# Sheet.net
KiCad netlist of a schematic drawn in Altium Designer
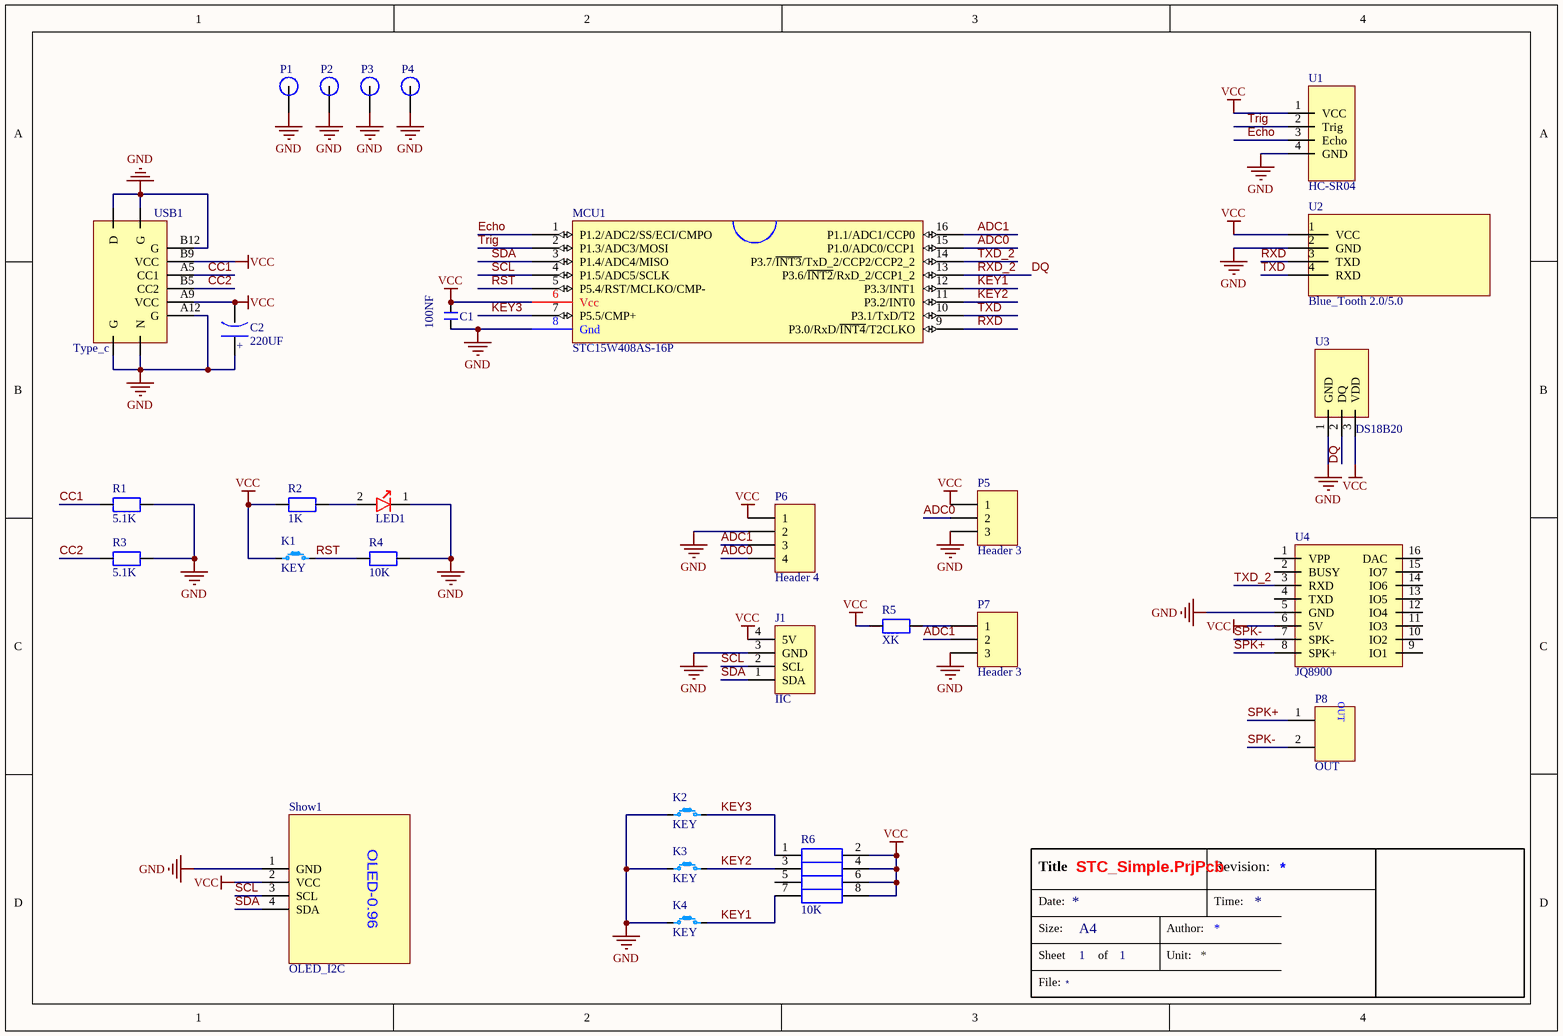
[diagram p0: Sheet.SchDoc]

(export (version "E")
  (design (tool "Eeschema 10.0.6"))
  (components
    (comp (ref "C1")
      (value "100NF")
      (footprint "CAP_0603")
      (description "CAP  12~50V")
      (libsource (lib "User") (part "CAP"))
    )
    (comp (ref "C2")
      (value "220UF")
      (footprint "CAP_PR_2.5_6.3_RA")
      (description "CAP 12V ~ 50V   电解电容")
      (libsource (lib "User") (part "CAP_BIG"))
    )
    (comp (ref "J1")
      (value "IIC")
      (footprint "IIC-XH2.54-4PIN")
      (description "Heard")
      (libsource (lib "User") (part "IIC"))
    )
    (comp (ref "K1")
      (value "KEY")
      (footprint "KEY_SMD")
      (description "Key")
      (libsource (lib "User") (part "KEY"))
    )
    (comp (ref "K2")
      (value "KEY")
      (footprint "SW_PB_3X6")
      (description "Key")
      (libsource (lib "User") (part "KEY"))
    )
    (comp (ref "K3")
      (value "KEY")
      (footprint "SW_PB_3X6")
      (description "Key")
      (libsource (lib "User") (part "KEY"))
    )
    (comp (ref "K4")
      (value "KEY")
      (footprint "SW_PB_3X6")
      (description "Key")
      (libsource (lib "User") (part "KEY"))
    )
    (comp (ref "LED1")
      (value "LED_R/G/B/Y")
      (footprint "LED_0603_R")
      (description "LED")
      (libsource (lib "User") (part "LED_SMT"))
    )
    (comp (ref "MCU1")
      (value "STC15W408AS-16P")
      (footprint "SOIC_16")
      (description "MCU")
      (libsource (lib "User") (part "STC15W-16"))
    )
    (comp (ref "P1")
      (value "铜柱6m")
      (footprint "M3x6_L-Type")
      (description "IN-OUT")
      (libsource (lib "User") (part "Pillar"))
    )
    (comp (ref "P2")
      (value "铜柱6m")
      (footprint "M3x6_L-Type")
      (description "IN-OUT")
      (libsource (lib "User") (part "Pillar"))
    )
    (comp (ref "P3")
      (value "铜柱6m")
      (footprint "M3x6_L-Type")
      (description "IN-OUT")
      (libsource (lib "User") (part "Pillar"))
    )
    (comp (ref "P4")
      (value "铜柱6m")
      (footprint "M3x6_L-Type")
      (description "IN-OUT")
      (libsource (lib "User") (part "Pillar"))
    )
    (comp (ref "P5")
      (value "Header 3")
      (footprint "Header 2.54X3")
      (description "Header, 3-Pin")
      (fields (field (name "PUBLISHER") "Altium Limited"))
      (libsource (lib "Miscellaneous Connectors") (part "Header 3"))
    )
    (comp (ref "P6")
      (value "Header 4")
      (footprint "Header F 2.54X4")
      (description "Header, 4-Pin")
      (fields (field (name "PUBLISHER") "Altium Limited"))
      (libsource (lib "Miscellaneous Connectors") (part "Header 4"))
    )
    (comp (ref "P7")
      (value "Header 3")
      (footprint "Header 2.54X3")
      (description "Header, 3-Pin")
      (fields (field (name "PUBLISHER") "Altium Limited"))
      (libsource (lib "Miscellaneous Connectors") (part "Header 3"))
    )
    (comp (ref "P8")
      (value "OUT")
      (footprint "XH2.54-WI-2P")
      (description "Header")
      (libsource (lib "User") (part "OUT_2PIN"))
    )
    (comp (ref "R1")
      (value "5.1K")
      (footprint "RESC_0603_2")
      (description "RES 贴片")
      (libsource (lib "User") (part "RES"))
    )
    (comp (ref "R2")
      (value "1K")
      (footprint "RESC_0603_2")
      (description "RES 贴片")
      (libsource (lib "User") (part "RES"))
    )
    (comp (ref "R3")
      (value "5.1K")
      (footprint "RESC_0603_2")
      (description "RES 贴片")
      (libsource (lib "User") (part "RES"))
    )
    (comp (ref "R4")
      (value "10K")
      (footprint "RESC_0603_2")
      (description "RES 贴片")
      (libsource (lib "User") (part "RES"))
    )
    (comp (ref "R5")
      (value "XK")
      (footprint "RESC_0603_2")
      (description "RES 贴片")
      (libsource (lib "User") (part "RES"))
    )
    (comp (ref "R6")
      (value "10K")
      (footprint "RESC_0603_4")
      (description "RES")
      (libsource (lib "User") (part "RES_P4"))
    )
    (comp (ref "Show1")
      (value "OLED_I2C")
      (footprint "OLED_I2C")
      (description "MODE")
      (libsource (lib "User") (part "OLED_I2C"))
    )
    (comp (ref "U1")
      (value "HC-SR04")
      (footprint "Ultrasonic")
      (description "Mode")
      (libsource (lib "User") (part "Ultrasonic"))
    )
    (comp (ref "U2")
      (value "Blue_Tooth 2.0/5.0")
      (footprint "uart-Haerd")
      (description "MODE")
      (libsource (lib "User") (part "HC-02/06"))
    )
    (comp (ref "U3")
      (value "DS18B20")
      (footprint "TO_92B")
      (description "MODE")
      (libsource (lib "User") (part "DS18B20"))
    )
    (comp (ref "U4")
      (value "JQ8900")
      (footprint "SpkMo")
      (description "MODE")
      (libsource (lib "User") (part "SPKMO_8900"))
    )
    (comp (ref "USB1")
      (value "Type_c")
      (footprint "USB-Type-c_6P")
      (description "USB")
      (libsource (lib "User") (part "USB-Type_c-6PIn"))
    )
  )
  (nets
    (net (code "1") (name "/ADC0") (class "Default")
      (node (ref "MCU1") (pin "15") (pinfunction "P1.0/ADC0/CCP1_15") (pintype "bidirectional"))
      (node (ref "P5") (pin "2") (pinfunction "2_2") (pintype "passive"))
      (node (ref "P6") (pin "4") (pinfunction "4_4") (pintype "passive"))
    )
    (net (code "2") (name "/ADC1") (class "Default")
      (node (ref "MCU1") (pin "16") (pinfunction "P1.1/ADC1/CCP0_16") (pintype "bidirectional"))
      (node (ref "P6") (pin "3") (pinfunction "3_3") (pintype "passive"))
      (node (ref "P7") (pin "2") (pinfunction "2_2") (pintype "passive"))
    )
    (net (code "3") (name "/CC1") (class "Default")
      (node (ref "R1") (pin "1") (pinfunction "1_1") (pintype "passive"))
      (node (ref "USB1") (pin "A5") (pinfunction "CC1_A5") (pintype "passive"))
    )
    (net (code "4") (name "/CC2") (class "Default")
      (node (ref "R3") (pin "1") (pinfunction "1_1") (pintype "passive"))
      (node (ref "USB1") (pin "B5") (pinfunction "CC2_B5") (pintype "passive"))
    )
    (net (code "5") (name "/DQ") (class "Default")
      (node (ref "MCU1") (pin "13") (pinfunction "P3.6/~{INT2}/RxD_2/CCP1_2_13") (pintype "bidirectional"))
      (node (ref "U3") (pin "2") (pinfunction "DQ_2") (pintype "passive"))
    )
    (net (code "6") (name "/Echo") (class "Default")
      (node (ref "MCU1") (pin "1") (pinfunction "P1.2/ADC2/SS/ECI/CMPO_1") (pintype "bidirectional"))
      (node (ref "U1") (pin "3") (pinfunction "Echo_3") (pintype "passive"))
    )
    (net (code "7") (name "/KEY1") (class "Default")
      (node (ref "K4") (pin "1") (pintype "passive"))
      (node (ref "MCU1") (pin "12") (pinfunction "P3.3/INT1_12") (pintype "bidirectional"))
      (node (ref "R6") (pin "7") (pinfunction "7_7") (pintype "passive"))
    )
    (net (code "8") (name "/KEY2") (class "Default")
      (node (ref "K3") (pin "1") (pintype "passive"))
      (node (ref "MCU1") (pin "11") (pinfunction "P3.2/INT0_11") (pintype "bidirectional"))
      (node (ref "R6") (pin "3") (pinfunction "3_3") (pintype "passive"))
    )
    (net (code "9") (name "/KEY3") (class "Default")
      (node (ref "K2") (pin "1") (pintype "passive"))
      (node (ref "MCU1") (pin "7") (pinfunction "P5.5/CMP+_7") (pintype "bidirectional"))
      (node (ref "R6") (pin "1") (pinfunction "1_1") (pintype "passive"))
    )
    (net (code "10") (name "/RST") (class "Default")
      (node (ref "K1") (pin "1") (pintype "passive"))
      (node (ref "MCU1") (pin "5") (pinfunction "P5.4/RST/MCLKO/CMP-_5") (pintype "bidirectional"))
      (node (ref "R4") (pin "1") (pinfunction "1_1") (pintype "passive"))
    )
    (net (code "11") (name "/RXD") (class "Default")
      (node (ref "MCU1") (pin "9") (pinfunction "P3.0/RxD/~{INT4}/T2CLKO_9") (pintype "bidirectional"))
      (node (ref "U2") (pin "3") (pinfunction "TXD_3") (pintype "passive"))
    )
    (net (code "12") (name "/SCL") (class "Default")
      (node (ref "J1") (pin "2") (pinfunction "SCL_2") (pintype "passive"))
      (node (ref "MCU1") (pin "4") (pinfunction "P1.5/ADC5/SCLK_4") (pintype "bidirectional"))
      (node (ref "Show1") (pin "3") (pinfunction "SCL_3") (pintype "passive"))
    )
    (net (code "13") (name "/SDA") (class "Default")
      (node (ref "J1") (pin "1") (pinfunction "SDA_1") (pintype "passive"))
      (node (ref "MCU1") (pin "3") (pinfunction "P1.4/ADC4/MISO_3") (pintype "bidirectional"))
      (node (ref "Show1") (pin "4") (pinfunction "SDA_4") (pintype "passive"))
    )
    (net (code "14") (name "/SPK+") (class "Default")
      (node (ref "P8") (pin "1") (pintype "passive"))
      (node (ref "U4") (pin "8") (pinfunction "SPK+_8") (pintype "passive"))
    )
    (net (code "15") (name "/SPK-") (class "Default")
      (node (ref "P8") (pin "2") (pintype "passive"))
      (node (ref "U4") (pin "7") (pinfunction "SPK-_7") (pintype "passive"))
    )
    (net (code "16") (name "/TXD") (class "Default")
      (node (ref "MCU1") (pin "10") (pinfunction "P3.1/TxD/T2_10") (pintype "bidirectional"))
      (node (ref "U2") (pin "4") (pinfunction "RXD_4") (pintype "passive"))
    )
    (net (code "17") (name "/TXD_2") (class "Default")
      (node (ref "MCU1") (pin "14") (pinfunction "P3.7/~{INT3}/TxD_2/CCP2/CCP2_2_14") (pintype "bidirectional"))
      (node (ref "U4") (pin "3") (pinfunction "RXD_3") (pintype "passive"))
    )
    (net (code "18") (name "/Trig") (class "Default")
      (node (ref "MCU1") (pin "2") (pinfunction "P1.3/ADC3/MOSI_2") (pintype "bidirectional"))
      (node (ref "U1") (pin "2") (pinfunction "Trig_2") (pintype "passive"))
    )
    (net (code "19") (name "GND") (class "Default")
      (node (ref "C1") (pin "1") (pinfunction "0_1") (pintype "passive"))
      (node (ref "C2") (pin "1") (pinfunction "0_1") (pintype "passive"))
      (node (ref "J1") (pin "3") (pinfunction "GND_3") (pintype "passive"))
      (node (ref "K2") (pin "2") (pintype "passive"))
      (node (ref "K3") (pin "2") (pintype "passive"))
      (node (ref "K4") (pin "2") (pintype "passive"))
      (node (ref "LED1") (pin "1") (pinfunction "-_1") (pintype "passive"))
      (node (ref "MCU1") (pin "8") (pinfunction "Gnd_8") (pintype "power_in"))
      (node (ref "P1") (pin "1") (pinfunction "IO_1") (pintype "passive"))
      (node (ref "P2") (pin "1") (pinfunction "IO_1") (pintype "passive"))
      (node (ref "P3") (pin "1") (pinfunction "IO_1") (pintype "passive"))
      (node (ref "P4") (pin "1") (pinfunction "IO_1") (pintype "passive"))
      (node (ref "P5") (pin "3") (pinfunction "3_3") (pintype "passive"))
      (node (ref "P6") (pin "2") (pinfunction "2_2") (pintype "passive"))
      (node (ref "P7") (pin "3") (pinfunction "3_3") (pintype "passive"))
      (node (ref "R1") (pin "2") (pinfunction "2_2") (pintype "passive"))
      (node (ref "R3") (pin "2") (pinfunction "2_2") (pintype "passive"))
      (node (ref "R4") (pin "2") (pinfunction "2_2") (pintype "passive"))
      (node (ref "Show1") (pin "1") (pinfunction "GND_1") (pintype "passive"))
      (node (ref "U1") (pin "4") (pinfunction "GND_4") (pintype "passive"))
      (node (ref "U2") (pin "2") (pinfunction "GND_2") (pintype "passive"))
      (node (ref "U3") (pin "1") (pinfunction "GND_1") (pintype "passive"))
      (node (ref "U4") (pin "5") (pinfunction "GND_5") (pintype "passive"))
      (node (ref "USB1") (pin "A") (pinfunction "G_A") (pintype "passive"))
      (node (ref "USB1") (pin "A12") (pinfunction "G_A12") (pintype "passive"))
      (node (ref "USB1") (pin "B") (pinfunction "N_B") (pintype "passive"))
      (node (ref "USB1") (pin "B12") (pinfunction "G_B12") (pintype "passive"))
      (node (ref "USB1") (pin "C") (pinfunction "D_C") (pintype "passive"))
      (node (ref "USB1") (pin "D") (pinfunction "G_D") (pintype "passive"))
    )
    (net (code "20") (name "Net-(LED1-+)") (class "Default")
      (node (ref "LED1") (pin "2") (pinfunction "+_2") (pintype "passive"))
      (node (ref "R2") (pin "2") (pinfunction "2_2") (pintype "passive"))
    )
    (net (code "21") (name "Net-(P7-Pad1)") (class "Default")
      (node (ref "P7") (pin "1") (pinfunction "1_1") (pintype "passive"))
      (node (ref "R5") (pin "2") (pinfunction "2_2") (pintype "passive"))
    )
    (net (code "22") (name "VCC") (class "Default")
      (node (ref "C1") (pin "2") (pinfunction "0_2") (pintype "passive"))
      (node (ref "C2") (pin "2") (pinfunction "0_2") (pintype "passive"))
      (node (ref "J1") (pin "4") (pinfunction "5V_4") (pintype "passive"))
      (node (ref "K1") (pin "2") (pintype "passive"))
      (node (ref "MCU1") (pin "6") (pinfunction "Vcc_6") (pintype "power_in"))
      (node (ref "P5") (pin "1") (pinfunction "1_1") (pintype "passive"))
      (node (ref "P6") (pin "1") (pinfunction "1_1") (pintype "passive"))
      (node (ref "R2") (pin "1") (pinfunction "1_1") (pintype "passive"))
      (node (ref "R5") (pin "1") (pinfunction "1_1") (pintype "passive"))
      (node (ref "R6") (pin "2") (pinfunction "2_2") (pintype "passive"))
      (node (ref "R6") (pin "4") (pinfunction "4_4") (pintype "passive"))
      (node (ref "R6") (pin "6") (pinfunction "6_6") (pintype "passive"))
      (node (ref "R6") (pin "8") (pinfunction "8_8") (pintype "passive"))
      (node (ref "Show1") (pin "2") (pinfunction "VCC_2") (pintype "passive"))
      (node (ref "U1") (pin "1") (pinfunction "VCC_1") (pintype "passive"))
      (node (ref "U2") (pin "1") (pinfunction "VCC_1") (pintype "passive"))
      (node (ref "U3") (pin "3") (pinfunction "VDD_3") (pintype "passive"))
      (node (ref "U4") (pin "6") (pinfunction "5V_6") (pintype "passive"))
      (node (ref "USB1") (pin "A9") (pinfunction "VCC_A9") (pintype "passive"))
      (node (ref "USB1") (pin "B9") (pinfunction "VCC_B9") (pintype "passive"))
    )
    (net (code "23") (name "unconnected-(R6-Pad5)") (class "Default")
      (node (ref "R6") (pin "5") (pinfunction "5_5") (pintype "passive"))
    )
    (net (code "24") (name "unconnected-(U4-BUSY-Pad2)") (class "Default")
      (node (ref "U4") (pin "2") (pinfunction "BUSY_2") (pintype "passive"))
    )
    (net (code "25") (name "unconnected-(U4-DAC-Pad16)") (class "Default")
      (node (ref "U4") (pin "16") (pinfunction "DAC_16") (pintype "passive"))
    )
    (net (code "26") (name "unconnected-(U4-IO1-Pad9)") (class "Default")
      (node (ref "U4") (pin "9") (pinfunction "IO1_9") (pintype "passive"))
    )
    (net (code "27") (name "unconnected-(U4-IO2-Pad10)") (class "Default")
      (node (ref "U4") (pin "10") (pinfunction "IO2_10") (pintype "passive"))
    )
    (net (code "28") (name "unconnected-(U4-IO3-Pad11)") (class "Default")
      (node (ref "U4") (pin "11") (pinfunction "IO3_11") (pintype "passive"))
    )
    (net (code "29") (name "unconnected-(U4-IO4-Pad12)") (class "Default")
      (node (ref "U4") (pin "12") (pinfunction "IO4_12") (pintype "passive"))
    )
    (net (code "30") (name "unconnected-(U4-IO5-Pad13)") (class "Default")
      (node (ref "U4") (pin "13") (pinfunction "IO5_13") (pintype "passive"))
    )
    (net (code "31") (name "unconnected-(U4-IO6-Pad14)") (class "Default")
      (node (ref "U4") (pin "14") (pinfunction "IO6_14") (pintype "passive"))
    )
    (net (code "32") (name "unconnected-(U4-IO7-Pad15)") (class "Default")
      (node (ref "U4") (pin "15") (pinfunction "IO7_15") (pintype "passive"))
    )
    (net (code "33") (name "unconnected-(U4-TXD-Pad4)") (class "Default")
      (node (ref "U4") (pin "4") (pinfunction "TXD_4") (pintype "passive"))
    )
    (net (code "34") (name "unconnected-(U4-VPP-Pad1)") (class "Default")
      (node (ref "U4") (pin "1") (pinfunction "VPP_1") (pintype "passive"))
    )
  )
)
